# delay_generator.net
KiCad netlist of a schematic drawn in EAGLE
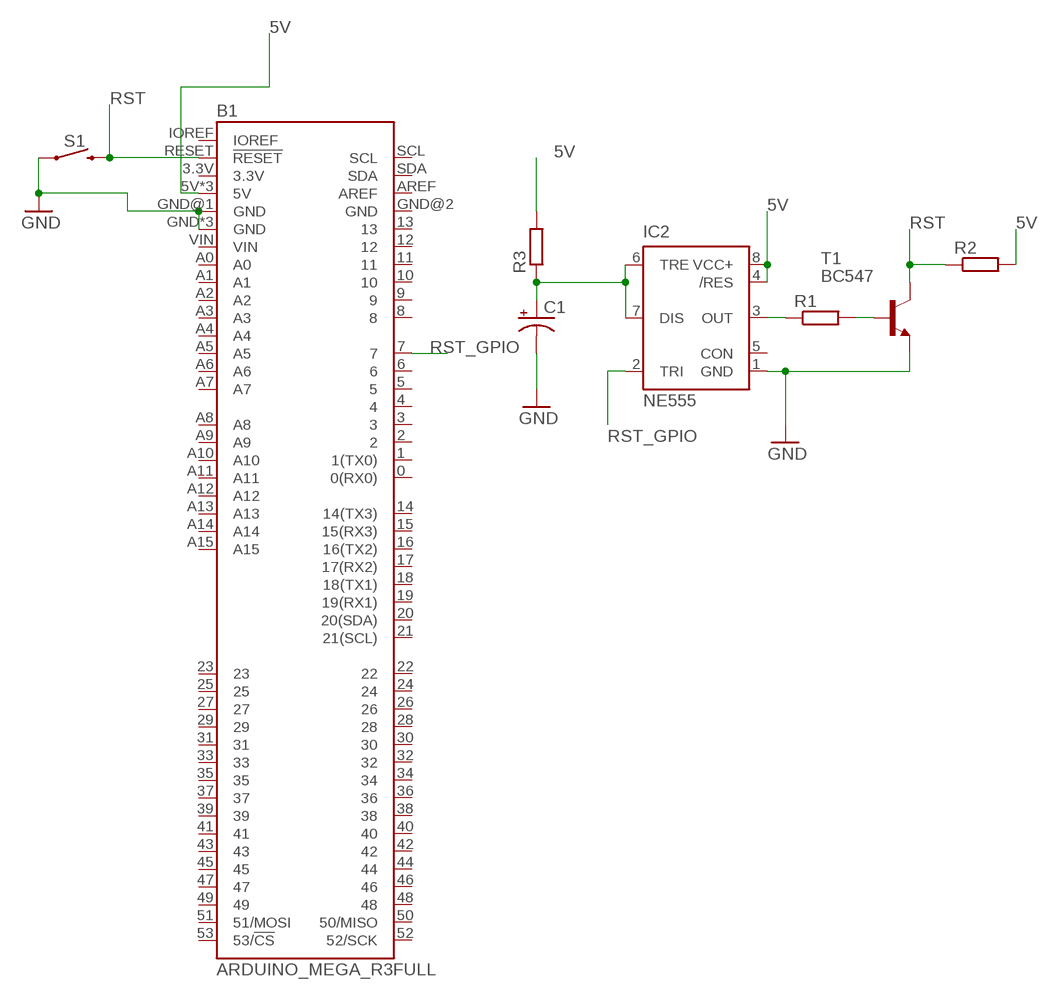
[diagram p0: schematic, sheet 1]

(export (version "E")
  (design (tool "Eeschema 10.0.6"))
  (components
    (comp (ref "B1")
      (value "ARDUINO_MEGA_R3FULL")
      (footprint "eagle-import:ARDUINO_MEGA_NO_SILK")
      (libsource (lib "eagle-import") (part "ARDUINO_MEGA_R3FULL"))
    )
    (comp (ref "C1")
      (value "CPOL-USE2.5-6")
      (footprint "eagle-import:E2,5-6")
      (libsource (lib "eagle-import") (part "CPOL-USE2.5-6"))
    )
    (comp (ref "IC2")
      (value "NE555")
      (footprint "eagle-import:DIL-08")
      (fields (field (name "MF") "Arrow Electronics") (field (name "MPN") "NE555N"))
      (libsource (lib "eagle-import") (part "NE555"))
    )
    (comp (ref "R1")
      (value "R-EU_0204/7")
      (footprint "eagle-import:0204_7")
      (libsource (lib "eagle-import") (part "R-EU_0204/7"))
    )
    (comp (ref "R2")
      (value "R-EU_0204/7")
      (footprint "eagle-import:0204_7")
      (libsource (lib "eagle-import") (part "R-EU_0204/7"))
    )
    (comp (ref "R3")
      (value "R-EU_0204/7")
      (footprint "eagle-import:0204_7")
      (libsource (lib "eagle-import") (part "R-EU_0204/7"))
    )
    (comp (ref "S1")
      (value "MOMENTARY-SWITCH-SPST-PTH-6.0MM")
      (footprint "eagle-import:TACTILE_SWITCH_PTH_6.0MM")
      (libsource (lib "eagle-import") (part "MOMENTARY-SWITCH-SPST-PTH-6.0MM"))
    )
    (comp (ref "T1")
      (value "BC547")
      (footprint "eagle-import:TO92")
      (libsource (lib "eagle-import") (part "BC547"))
    )
  )
  (nets
    (net (code "1") (name "/5V") (class "Default")
      (node (ref "B1") (pin "5V") (pinfunction "5V_5V") (pintype "bidirectional"))
      (node (ref "B1") (pin "5V@1") (pinfunction "5V_5V@1") (pintype "bidirectional"))
      (node (ref "B1") (pin "5V@2") (pinfunction "5V_5V@2") (pintype "bidirectional"))
      (node (ref "IC2") (pin "4") (pinfunction "/RES_4") (pintype "input"))
      (node (ref "IC2") (pin "8") (pinfunction "VCC+_8") (pintype "power_in"))
      (node (ref "R2") (pin "2") (pinfunction "2_2") (pintype "passive"))
      (node (ref "R3") (pin "2") (pinfunction "2_2") (pintype "passive"))
    )
    (net (code "2") (name "/RST") (class "Default")
      (node (ref "B1") (pin "RESET") (pinfunction "~{RESET}_RESET") (pintype "bidirectional"))
      (node (ref "R2") (pin "1") (pinfunction "1_1") (pintype "passive"))
      (node (ref "S1") (pin "3") (pinfunction "2_3") (pintype "passive"))
      (node (ref "T1") (pin "3") (pinfunction "C_3") (pintype "passive"))
    )
    (net (code "3") (name "/RST_GPIO") (class "Default")
      (node (ref "B1") (pin "7") (pinfunction "7_7") (pintype "bidirectional"))
      (node (ref "IC2") (pin "2") (pinfunction "TRI_2") (pintype "input"))
    )
    (net (code "4") (name "GND") (class "Default")
      (node (ref "B1") (pin "GND") (pinfunction "GND_GND") (pintype "bidirectional"))
      (node (ref "B1") (pin "GND@1") (pinfunction "GND_GND@1") (pintype "bidirectional"))
      (node (ref "B1") (pin "GND@3") (pinfunction "GND_GND@3") (pintype "bidirectional"))
      (node (ref "B1") (pin "GND@4") (pinfunction "GND_GND@4") (pintype "bidirectional"))
      (node (ref "C1") (pin "-") (pinfunction "-_-") (pintype "passive"))
      (node (ref "IC2") (pin "1") (pinfunction "GND_1") (pintype "power_in"))
      (node (ref "S1") (pin "1") (pinfunction "1_1") (pintype "passive"))
      (node (ref "T1") (pin "1") (pinfunction "E_1") (pintype "passive"))
    )
    (net (code "5") (name "Net-(IC2-DIS)") (class "Default")
      (node (ref "C1") (pin "+") (pinfunction "+_+") (pintype "passive"))
      (node (ref "IC2") (pin "6") (pinfunction "TRE_6") (pintype "input"))
      (node (ref "IC2") (pin "7") (pinfunction "DIS_7") (pintype "input"))
      (node (ref "R3") (pin "1") (pinfunction "1_1") (pintype "passive"))
    )
    (net (code "6") (name "Net-(IC2-OUT)") (class "Default")
      (node (ref "IC2") (pin "3") (pinfunction "OUT_3") (pintype "output"))
      (node (ref "R1") (pin "1") (pinfunction "1_1") (pintype "passive"))
    )
    (net (code "7") (name "Net-(T1-B)") (class "Default")
      (node (ref "R1") (pin "2") (pinfunction "2_2") (pintype "passive"))
      (node (ref "T1") (pin "2") (pinfunction "B_2") (pintype "passive"))
    )
    (net (code "8") (name "unconnected-(B1-0(RX0)-Pad0)") (class "Default")
      (node (ref "B1") (pin "0") (pinfunction "0(RX0)_0") (pintype "bidirectional"))
    )
    (net (code "9") (name "unconnected-(B1-1(TX0)-Pad1)") (class "Default")
      (node (ref "B1") (pin "1") (pinfunction "1(TX0)_1") (pintype "bidirectional"))
    )
    (net (code "10") (name "unconnected-(B1-14(TX3)-Pad14)") (class "Default")
      (node (ref "B1") (pin "14") (pinfunction "14(TX3)_14") (pintype "bidirectional"))
    )
    (net (code "11") (name "unconnected-(B1-15(RX3)-Pad15)") (class "Default")
      (node (ref "B1") (pin "15") (pinfunction "15(RX3)_15") (pintype "bidirectional"))
    )
    (net (code "12") (name "unconnected-(B1-16(TX2)-Pad16)") (class "Default")
      (node (ref "B1") (pin "16") (pinfunction "16(TX2)_16") (pintype "bidirectional"))
    )
    (net (code "13") (name "unconnected-(B1-17(RX2)-Pad17)") (class "Default")
      (node (ref "B1") (pin "17") (pinfunction "17(RX2)_17") (pintype "bidirectional"))
    )
    (net (code "14") (name "unconnected-(B1-18(TX1)-Pad18)") (class "Default")
      (node (ref "B1") (pin "18") (pinfunction "18(TX1)_18") (pintype "bidirectional"))
    )
    (net (code "15") (name "unconnected-(B1-19(RX1)-Pad19)") (class "Default")
      (node (ref "B1") (pin "19") (pinfunction "19(RX1)_19") (pintype "bidirectional"))
    )
    (net (code "16") (name "unconnected-(B1-20(SDA)-Pad20)") (class "Default")
      (node (ref "B1") (pin "20") (pinfunction "20(SDA)_20") (pintype "bidirectional"))
    )
    (net (code "17") (name "unconnected-(B1-21(SCL)-Pad21)") (class "Default")
      (node (ref "B1") (pin "21") (pinfunction "21(SCL)_21") (pintype "bidirectional"))
    )
    (net (code "18") (name "unconnected-(B1-50{slash}MISO-Pad50)") (class "Default")
      (node (ref "B1") (pin "50") (pinfunction "50/MISO_50") (pintype "bidirectional"))
    )
    (net (code "19") (name "unconnected-(B1-51{slash}MOSI-Pad51)") (class "Default")
      (node (ref "B1") (pin "51") (pinfunction "51/MOSI_51") (pintype "bidirectional"))
    )
    (net (code "20") (name "unconnected-(B1-52{slash}SCK-Pad52)") (class "Default")
      (node (ref "B1") (pin "52") (pinfunction "52/SCK_52") (pintype "bidirectional"))
    )
    (net (code "21") (name "unconnected-(B1-53{slash}~{CS}-Pad53)") (class "Default")
      (node (ref "B1") (pin "53") (pinfunction "53/~{CS}_53") (pintype "bidirectional"))
    )
    (net (code "22") (name "unconnected-(B1-GND-PadGND@2)") (class "Default")
      (node (ref "B1") (pin "GND@2") (pinfunction "GND_GND@2") (pintype "bidirectional"))
    )
    (net (code "23") (name "unconnected-(B1-Pad2)") (class "Default")
      (node (ref "B1") (pin "2") (pinfunction "2_2") (pintype "bidirectional"))
    )
    (net (code "24") (name "unconnected-(B1-Pad3)") (class "Default")
      (node (ref "B1") (pin "3") (pinfunction "3_3") (pintype "bidirectional"))
    )
    (net (code "25") (name "unconnected-(B1-Pad3.3V)") (class "Default")
      (node (ref "B1") (pin "3.3V") (pinfunction "3.3V_3.3V") (pintype "bidirectional"))
    )
    (net (code "26") (name "unconnected-(B1-Pad4)") (class "Default")
      (node (ref "B1") (pin "4") (pinfunction "4_4") (pintype "bidirectional"))
    )
    (net (code "27") (name "unconnected-(B1-Pad5)") (class "Default")
      (node (ref "B1") (pin "5") (pinfunction "5_5") (pintype "bidirectional"))
    )
    (net (code "28") (name "unconnected-(B1-Pad6)") (class "Default")
      (node (ref "B1") (pin "6") (pinfunction "6_6") (pintype "bidirectional"))
    )
    (net (code "29") (name "unconnected-(B1-Pad8)") (class "Default")
      (node (ref "B1") (pin "8") (pinfunction "8_8") (pintype "bidirectional"))
    )
    (net (code "30") (name "unconnected-(B1-Pad9)") (class "Default")
      (node (ref "B1") (pin "9") (pinfunction "9_9") (pintype "bidirectional"))
    )
    (net (code "31") (name "unconnected-(B1-Pad10)") (class "Default")
      (node (ref "B1") (pin "10") (pinfunction "10_10") (pintype "bidirectional"))
    )
    (net (code "32") (name "unconnected-(B1-Pad11)") (class "Default")
      (node (ref "B1") (pin "11") (pinfunction "11_11") (pintype "bidirectional"))
    )
    (net (code "33") (name "unconnected-(B1-Pad12)") (class "Default")
      (node (ref "B1") (pin "12") (pinfunction "12_12") (pintype "bidirectional"))
    )
    (net (code "34") (name "unconnected-(B1-Pad13)") (class "Default")
      (node (ref "B1") (pin "13") (pinfunction "13_13") (pintype "bidirectional"))
    )
    (net (code "35") (name "unconnected-(B1-Pad22)") (class "Default")
      (node (ref "B1") (pin "22") (pinfunction "22_22") (pintype "bidirectional"))
    )
    (net (code "36") (name "unconnected-(B1-Pad23)") (class "Default")
      (node (ref "B1") (pin "23") (pinfunction "23_23") (pintype "bidirectional"))
    )
    (net (code "37") (name "unconnected-(B1-Pad24)") (class "Default")
      (node (ref "B1") (pin "24") (pinfunction "24_24") (pintype "bidirectional"))
    )
    (net (code "38") (name "unconnected-(B1-Pad25)") (class "Default")
      (node (ref "B1") (pin "25") (pinfunction "25_25") (pintype "bidirectional"))
    )
    (net (code "39") (name "unconnected-(B1-Pad26)") (class "Default")
      (node (ref "B1") (pin "26") (pinfunction "26_26") (pintype "bidirectional"))
    )
    (net (code "40") (name "unconnected-(B1-Pad27)") (class "Default")
      (node (ref "B1") (pin "27") (pinfunction "27_27") (pintype "bidirectional"))
    )
    (net (code "41") (name "unconnected-(B1-Pad28)") (class "Default")
      (node (ref "B1") (pin "28") (pinfunction "28_28") (pintype "bidirectional"))
    )
    (net (code "42") (name "unconnected-(B1-Pad29)") (class "Default")
      (node (ref "B1") (pin "29") (pinfunction "29_29") (pintype "bidirectional"))
    )
    (net (code "43") (name "unconnected-(B1-Pad30)") (class "Default")
      (node (ref "B1") (pin "30") (pinfunction "30_30") (pintype "bidirectional"))
    )
    (net (code "44") (name "unconnected-(B1-Pad31)") (class "Default")
      (node (ref "B1") (pin "31") (pinfunction "31_31") (pintype "bidirectional"))
    )
    (net (code "45") (name "unconnected-(B1-Pad32)") (class "Default")
      (node (ref "B1") (pin "32") (pinfunction "32_32") (pintype "bidirectional"))
    )
    (net (code "46") (name "unconnected-(B1-Pad33)") (class "Default")
      (node (ref "B1") (pin "33") (pinfunction "33_33") (pintype "bidirectional"))
    )
    (net (code "47") (name "unconnected-(B1-Pad34)") (class "Default")
      (node (ref "B1") (pin "34") (pinfunction "34_34") (pintype "bidirectional"))
    )
    (net (code "48") (name "unconnected-(B1-Pad35)") (class "Default")
      (node (ref "B1") (pin "35") (pinfunction "35_35") (pintype "bidirectional"))
    )
    (net (code "49") (name "unconnected-(B1-Pad36)") (class "Default")
      (node (ref "B1") (pin "36") (pinfunction "36_36") (pintype "bidirectional"))
    )
    (net (code "50") (name "unconnected-(B1-Pad37)") (class "Default")
      (node (ref "B1") (pin "37") (pinfunction "37_37") (pintype "bidirectional"))
    )
    (net (code "51") (name "unconnected-(B1-Pad38)") (class "Default")
      (node (ref "B1") (pin "38") (pinfunction "38_38") (pintype "bidirectional"))
    )
    (net (code "52") (name "unconnected-(B1-Pad39)") (class "Default")
      (node (ref "B1") (pin "39") (pinfunction "39_39") (pintype "bidirectional"))
    )
    (net (code "53") (name "unconnected-(B1-Pad40)") (class "Default")
      (node (ref "B1") (pin "40") (pinfunction "40_40") (pintype "bidirectional"))
    )
    (net (code "54") (name "unconnected-(B1-Pad41)") (class "Default")
      (node (ref "B1") (pin "41") (pinfunction "41_41") (pintype "bidirectional"))
    )
    (net (code "55") (name "unconnected-(B1-Pad42)") (class "Default")
      (node (ref "B1") (pin "42") (pinfunction "42_42") (pintype "bidirectional"))
    )
    (net (code "56") (name "unconnected-(B1-Pad43)") (class "Default")
      (node (ref "B1") (pin "43") (pinfunction "43_43") (pintype "bidirectional"))
    )
    (net (code "57") (name "unconnected-(B1-Pad44)") (class "Default")
      (node (ref "B1") (pin "44") (pinfunction "44_44") (pintype "bidirectional"))
    )
    (net (code "58") (name "unconnected-(B1-Pad45)") (class "Default")
      (node (ref "B1") (pin "45") (pinfunction "45_45") (pintype "bidirectional"))
    )
    (net (code "59") (name "unconnected-(B1-Pad46)") (class "Default")
      (node (ref "B1") (pin "46") (pinfunction "46_46") (pintype "bidirectional"))
    )
    (net (code "60") (name "unconnected-(B1-Pad47)") (class "Default")
      (node (ref "B1") (pin "47") (pinfunction "47_47") (pintype "bidirectional"))
    )
    (net (code "61") (name "unconnected-(B1-Pad48)") (class "Default")
      (node (ref "B1") (pin "48") (pinfunction "48_48") (pintype "bidirectional"))
    )
    (net (code "62") (name "unconnected-(B1-Pad49)") (class "Default")
      (node (ref "B1") (pin "49") (pinfunction "49_49") (pintype "bidirectional"))
    )
    (net (code "63") (name "unconnected-(B1-PadA0)") (class "Default")
      (node (ref "B1") (pin "A0") (pinfunction "A0_A0") (pintype "bidirectional"))
    )
    (net (code "64") (name "unconnected-(B1-PadA1)") (class "Default")
      (node (ref "B1") (pin "A1") (pinfunction "A1_A1") (pintype "bidirectional"))
    )
    (net (code "65") (name "unconnected-(B1-PadA2)") (class "Default")
      (node (ref "B1") (pin "A2") (pinfunction "A2_A2") (pintype "bidirectional"))
    )
    (net (code "66") (name "unconnected-(B1-PadA3)") (class "Default")
      (node (ref "B1") (pin "A3") (pinfunction "A3_A3") (pintype "bidirectional"))
    )
    (net (code "67") (name "unconnected-(B1-PadA4)") (class "Default")
      (node (ref "B1") (pin "A4") (pinfunction "A4_A4") (pintype "bidirectional"))
    )
    (net (code "68") (name "unconnected-(B1-PadA5)") (class "Default")
      (node (ref "B1") (pin "A5") (pinfunction "A5_A5") (pintype "bidirectional"))
    )
    (net (code "69") (name "unconnected-(B1-PadA6)") (class "Default")
      (node (ref "B1") (pin "A6") (pinfunction "A6_A6") (pintype "bidirectional"))
    )
    (net (code "70") (name "unconnected-(B1-PadA7)") (class "Default")
      (node (ref "B1") (pin "A7") (pinfunction "A7_A7") (pintype "bidirectional"))
    )
    (net (code "71") (name "unconnected-(B1-PadA8)") (class "Default")
      (node (ref "B1") (pin "A8") (pinfunction "A8_A8") (pintype "bidirectional"))
    )
    (net (code "72") (name "unconnected-(B1-PadA9)") (class "Default")
      (node (ref "B1") (pin "A9") (pinfunction "A9_A9") (pintype "bidirectional"))
    )
    (net (code "73") (name "unconnected-(B1-PadA10)") (class "Default")
      (node (ref "B1") (pin "A10") (pinfunction "A10_A10") (pintype "bidirectional"))
    )
    (net (code "74") (name "unconnected-(B1-PadA11)") (class "Default")
      (node (ref "B1") (pin "A11") (pinfunction "A11_A11") (pintype "bidirectional"))
    )
    (net (code "75") (name "unconnected-(B1-PadA12)") (class "Default")
      (node (ref "B1") (pin "A12") (pinfunction "A12_A12") (pintype "bidirectional"))
    )
    (net (code "76") (name "unconnected-(B1-PadA13)") (class "Default")
      (node (ref "B1") (pin "A13") (pinfunction "A13_A13") (pintype "bidirectional"))
    )
    (net (code "77") (name "unconnected-(B1-PadA14)") (class "Default")
      (node (ref "B1") (pin "A14") (pinfunction "A14_A14") (pintype "bidirectional"))
    )
    (net (code "78") (name "unconnected-(B1-PadA15)") (class "Default")
      (node (ref "B1") (pin "A15") (pinfunction "A15_A15") (pintype "bidirectional"))
    )
    (net (code "79") (name "unconnected-(B1-PadAREF)") (class "Default")
      (node (ref "B1") (pin "AREF") (pinfunction "AREF_AREF") (pintype "bidirectional"))
    )
    (net (code "80") (name "unconnected-(B1-PadIOREF)") (class "Default")
      (node (ref "B1") (pin "IOREF") (pinfunction "IOREF_IOREF") (pintype "bidirectional"))
    )
    (net (code "81") (name "unconnected-(B1-PadSCL)") (class "Default")
      (node (ref "B1") (pin "SCL") (pinfunction "SCL_SCL") (pintype "bidirectional"))
    )
    (net (code "82") (name "unconnected-(B1-PadSDA)") (class "Default")
      (node (ref "B1") (pin "SDA") (pinfunction "SDA_SDA") (pintype "bidirectional"))
    )
    (net (code "83") (name "unconnected-(B1-PadVIN)") (class "Default")
      (node (ref "B1") (pin "VIN") (pinfunction "VIN_VIN") (pintype "bidirectional"))
    )
    (net (code "84") (name "unconnected-(IC2-CON-Pad5)") (class "Default")
      (node (ref "IC2") (pin "5") (pinfunction "CON_5") (pintype "input"))
    )
  )
)
